# placa_nano.net
KiCad netlist of a schematic drawn in EAGLE
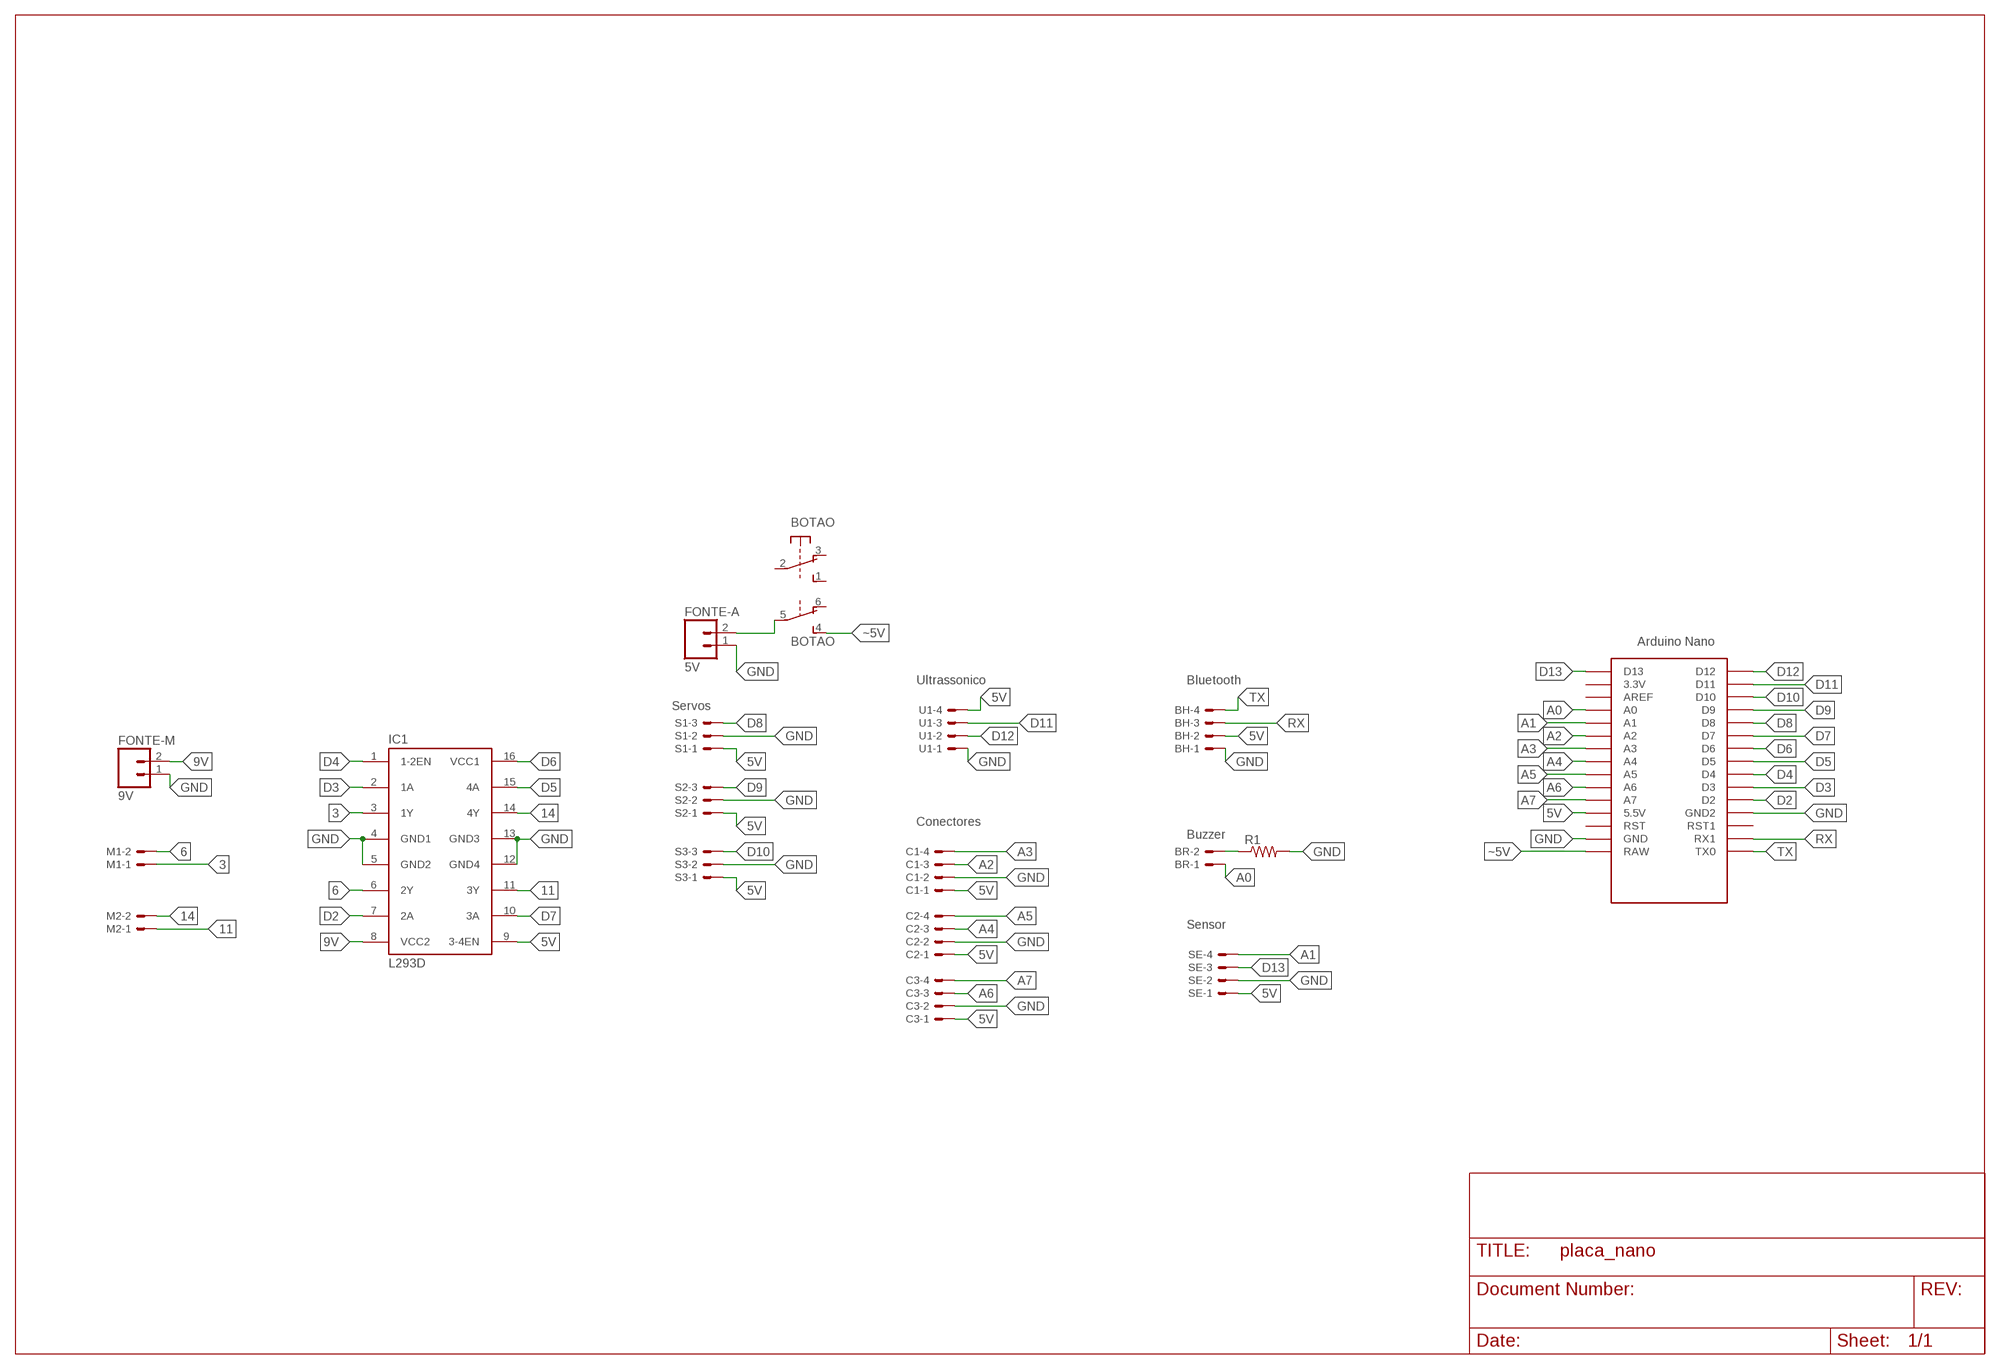
[diagram p0: schematic, sheet 1]

(export (version "E")
  (design (tool "Eeschema 10.0.6"))
  (components
    (comp (ref "BH")
      (value "22-23-2041")
      (footprint "eagle-import:22-23-2041")
      (fields (field (name "MF") "MOLEX"))
      (libsource (lib "eagle-import") (part "22-23-2041"))
    )
    (comp (ref "BOTAO")
      (value "9077-2")
      (footprint "eagle-import:9077-2")
      (libsource (lib "eagle-import") (part "9077-2"))
    )
    (comp (ref "BR")
      (value "22-23-2021")
      (footprint "eagle-import:22-23-2021")
      (fields (field (name "MF") "MOLEX"))
      (libsource (lib "eagle-import") (part "22-23-2021"))
    )
    (comp (ref "C1")
      (value "22-23-2041")
      (footprint "eagle-import:22-23-2041")
      (fields (field (name "MF") "MOLEX"))
      (libsource (lib "eagle-import") (part "22-23-2041"))
    )
    (comp (ref "C2")
      (value "22-23-2041")
      (footprint "eagle-import:22-23-2041")
      (fields (field (name "MF") "MOLEX"))
      (libsource (lib "eagle-import") (part "22-23-2041"))
    )
    (comp (ref "C3")
      (value "22-23-2041")
      (footprint "eagle-import:22-23-2041")
      (fields (field (name "MF") "MOLEX"))
      (libsource (lib "eagle-import") (part "22-23-2041"))
    )
    (comp (ref "FONTE-A")
      (value "5V")
      (footprint "eagle-import:02P")
      (libsource (lib "eagle-import") (part "M02"))
    )
    (comp (ref "FONTE-M")
      (value "9V")
      (footprint "eagle-import:02P")
      (libsource (lib "eagle-import") (part "M02"))
    )
    (comp (ref "IC1")
      (value "L293D")
      (footprint "eagle-import:DIL16")
      (libsource (lib "eagle-import") (part "L293D"))
    )
    (comp (ref "M1")
      (value "22-23-2021")
      (footprint "eagle-import:22-23-2021")
      (fields (field (name "MF") "MOLEX"))
      (libsource (lib "eagle-import") (part "22-23-2021"))
    )
    (comp (ref "M2")
      (value "22-23-2021")
      (footprint "eagle-import:22-23-2021")
      (fields (field (name "MF") "MOLEX"))
      (libsource (lib "eagle-import") (part "22-23-2021"))
    )
    (comp (ref "R1")
      (value "R-US_0207/10")
      (footprint "eagle-import:0207_10")
      (libsource (lib "eagle-import") (part "R-US_0207/10"))
    )
    (comp (ref "S1")
      (value "22-23-2031")
      (footprint "eagle-import:22-23-2031")
      (fields (field (name "MF") "MOLEX"))
      (libsource (lib "eagle-import") (part "22-23-2031"))
    )
    (comp (ref "S2")
      (value "22-23-2031")
      (footprint "eagle-import:22-23-2031")
      (fields (field (name "MF") "MOLEX"))
      (libsource (lib "eagle-import") (part "22-23-2031"))
    )
    (comp (ref "S3")
      (value "22-23-2031")
      (footprint "eagle-import:22-23-2031")
      (fields (field (name "MF") "MOLEX"))
      (libsource (lib "eagle-import") (part "22-23-2031"))
    )
    (comp (ref "SE")
      (value "22-23-2041")
      (footprint "eagle-import:22-23-2041")
      (fields (field (name "MF") "MOLEX"))
      (libsource (lib "eagle-import") (part "22-23-2041"))
    )
    (comp (ref "U$1")
      (value "NANO")
      (footprint "eagle-import:NANO")
      (libsource (lib "eagle-import") (part "NANO"))
    )
    (comp (ref "U1")
      (value "22-23-2041")
      (footprint "eagle-import:22-23-2041")
      (fields (field (name "MF") "MOLEX"))
      (libsource (lib "eagle-import") (part "22-23-2041"))
    )
  )
  (nets
    (net (code "1") (name "/~{5V}") (class "Default")
      (node (ref "BOTAO") (pin "4") (pinfunction "S_4") (pintype "passive"))
      (node (ref "BOTAO") (pin "5") (pinfunction "P_5") (pintype "passive"))
      (node (ref "FONTE-A") (pin "2") (pinfunction "2_2") (pintype "passive"))
      (node (ref "U$1") (pin "RAW") (pinfunction "RAW_RAW") (pintype "bidirectional"))
    )
    (net (code "2") (name "3") (class "Default")
      (node (ref "IC1") (pin "3") (pinfunction "1Y_3") (pintype "output"))
      (node (ref "M1") (pin "1") (pinfunction "S_1") (pintype "passive"))
    )
    (net (code "3") (name "5V") (class "Default")
      (node (ref "BH") (pin "2") (pinfunction "S_2") (pintype "passive"))
      (node (ref "C1") (pin "1") (pinfunction "S_1") (pintype "passive"))
      (node (ref "C2") (pin "1") (pinfunction "S_1") (pintype "passive"))
      (node (ref "C3") (pin "1") (pinfunction "S_1") (pintype "passive"))
      (node (ref "IC1") (pin "9") (pinfunction "3-4EN_9") (pintype "input"))
      (node (ref "S1") (pin "1") (pinfunction "S_1") (pintype "passive"))
      (node (ref "S2") (pin "1") (pinfunction "S_1") (pintype "passive"))
      (node (ref "S3") (pin "1") (pinfunction "S_1") (pintype "passive"))
      (node (ref "SE") (pin "1") (pinfunction "S_1") (pintype "passive"))
      (node (ref "U$1") (pin "5V") (pinfunction "5.5V_5V") (pintype "bidirectional"))
      (node (ref "U1") (pin "4") (pinfunction "S_4") (pintype "passive"))
    )
    (net (code "4") (name "6") (class "Default")
      (node (ref "IC1") (pin "6") (pinfunction "2Y_6") (pintype "output"))
      (node (ref "M1") (pin "2") (pinfunction "S_2") (pintype "passive"))
    )
    (net (code "5") (name "9V") (class "Default")
      (node (ref "FONTE-M") (pin "2") (pinfunction "2_2") (pintype "passive"))
      (node (ref "IC1") (pin "8") (pinfunction "VCC2_8") (pintype "power_in"))
    )
    (net (code "6") (name "11") (class "Default")
      (node (ref "IC1") (pin "11") (pinfunction "3Y_11") (pintype "output"))
      (node (ref "M2") (pin "1") (pinfunction "S_1") (pintype "passive"))
    )
    (net (code "7") (name "14") (class "Default")
      (node (ref "IC1") (pin "14") (pinfunction "4Y_14") (pintype "output"))
      (node (ref "M2") (pin "2") (pinfunction "S_2") (pintype "passive"))
    )
    (net (code "8") (name "A0") (class "Default")
      (node (ref "BR") (pin "1") (pinfunction "S_1") (pintype "passive"))
      (node (ref "U$1") (pin "A0") (pinfunction "A0_A0") (pintype "bidirectional"))
    )
    (net (code "9") (name "A1") (class "Default")
      (node (ref "SE") (pin "4") (pinfunction "S_4") (pintype "passive"))
      (node (ref "U$1") (pin "A1") (pinfunction "A1_A1") (pintype "bidirectional"))
    )
    (net (code "10") (name "A2") (class "Default")
      (node (ref "C1") (pin "3") (pinfunction "S_3") (pintype "passive"))
      (node (ref "U$1") (pin "A2") (pinfunction "A2_A2") (pintype "bidirectional"))
    )
    (net (code "11") (name "A3") (class "Default")
      (node (ref "C1") (pin "4") (pinfunction "S_4") (pintype "passive"))
      (node (ref "U$1") (pin "A3") (pinfunction "A3_A3") (pintype "bidirectional"))
    )
    (net (code "12") (name "A4") (class "Default")
      (node (ref "C2") (pin "3") (pinfunction "S_3") (pintype "passive"))
      (node (ref "U$1") (pin "A4") (pinfunction "A4_A4") (pintype "bidirectional"))
    )
    (net (code "13") (name "A5") (class "Default")
      (node (ref "C2") (pin "4") (pinfunction "S_4") (pintype "passive"))
      (node (ref "U$1") (pin "A5") (pinfunction "A5_A5") (pintype "bidirectional"))
    )
    (net (code "14") (name "A6") (class "Default")
      (node (ref "C3") (pin "3") (pinfunction "S_3") (pintype "passive"))
      (node (ref "U$1") (pin "A6") (pinfunction "A6_A6") (pintype "bidirectional"))
    )
    (net (code "15") (name "A7") (class "Default")
      (node (ref "C3") (pin "4") (pinfunction "S_4") (pintype "passive"))
      (node (ref "U$1") (pin "A7") (pinfunction "A7_A7") (pintype "bidirectional"))
    )
    (net (code "16") (name "D2") (class "Default")
      (node (ref "IC1") (pin "7") (pinfunction "2A_7") (pintype "input"))
      (node (ref "U$1") (pin "D2") (pinfunction "D2_D2") (pintype "bidirectional"))
    )
    (net (code "17") (name "D3") (class "Default")
      (node (ref "IC1") (pin "2") (pinfunction "1A_2") (pintype "input"))
      (node (ref "U$1") (pin "D3") (pinfunction "D3_D3") (pintype "bidirectional"))
    )
    (net (code "18") (name "D4") (class "Default")
      (node (ref "IC1") (pin "1") (pinfunction "1-2EN_1") (pintype "input"))
      (node (ref "U$1") (pin "D4") (pinfunction "D4_D4") (pintype "bidirectional"))
    )
    (net (code "19") (name "D5") (class "Default")
      (node (ref "IC1") (pin "15") (pinfunction "4A_15") (pintype "input"))
      (node (ref "U$1") (pin "D5") (pinfunction "D5_D5") (pintype "bidirectional"))
    )
    (net (code "20") (name "D6") (class "Default")
      (node (ref "IC1") (pin "16") (pinfunction "VCC1_16") (pintype "power_in"))
      (node (ref "U$1") (pin "D6") (pinfunction "D6_D6") (pintype "bidirectional"))
    )
    (net (code "21") (name "D7") (class "Default")
      (node (ref "IC1") (pin "10") (pinfunction "3A_10") (pintype "input"))
      (node (ref "U$1") (pin "D7") (pinfunction "D7_D7") (pintype "bidirectional"))
    )
    (net (code "22") (name "D8") (class "Default")
      (node (ref "S1") (pin "3") (pinfunction "S_3") (pintype "passive"))
      (node (ref "U$1") (pin "D8") (pinfunction "D8_D8") (pintype "bidirectional"))
    )
    (net (code "23") (name "D9") (class "Default")
      (node (ref "S2") (pin "3") (pinfunction "S_3") (pintype "passive"))
      (node (ref "U$1") (pin "D9") (pinfunction "D9_D9") (pintype "bidirectional"))
    )
    (net (code "24") (name "D10") (class "Default")
      (node (ref "S3") (pin "3") (pinfunction "S_3") (pintype "passive"))
      (node (ref "U$1") (pin "D10") (pinfunction "D10_D10") (pintype "bidirectional"))
    )
    (net (code "25") (name "D11") (class "Default")
      (node (ref "U$1") (pin "D11") (pinfunction "D11_D11") (pintype "bidirectional"))
      (node (ref "U1") (pin "3") (pinfunction "S_3") (pintype "passive"))
    )
    (net (code "26") (name "D12") (class "Default")
      (node (ref "U$1") (pin "D12") (pinfunction "D12_D12") (pintype "bidirectional"))
      (node (ref "U1") (pin "2") (pinfunction "S_2") (pintype "passive"))
    )
    (net (code "27") (name "D13") (class "Default")
      (node (ref "SE") (pin "3") (pinfunction "S_3") (pintype "passive"))
      (node (ref "U$1") (pin "D13") (pinfunction "D13_D13") (pintype "bidirectional"))
    )
    (net (code "28") (name "GND") (class "Default")
      (node (ref "BH") (pin "1") (pinfunction "S_1") (pintype "passive"))
      (node (ref "C1") (pin "2") (pinfunction "S_2") (pintype "passive"))
      (node (ref "C2") (pin "2") (pinfunction "S_2") (pintype "passive"))
      (node (ref "C3") (pin "2") (pinfunction "S_2") (pintype "passive"))
      (node (ref "FONTE-A") (pin "1") (pinfunction "1_1") (pintype "passive"))
      (node (ref "FONTE-M") (pin "1") (pinfunction "1_1") (pintype "passive"))
      (node (ref "IC1") (pin "12") (pinfunction "GND4_12") (pintype "power_in"))
      (node (ref "IC1") (pin "13") (pinfunction "GND3_13") (pintype "power_in"))
      (node (ref "IC1") (pin "4") (pinfunction "GND1_4") (pintype "power_in"))
      (node (ref "IC1") (pin "5") (pinfunction "GND2_5") (pintype "power_in"))
      (node (ref "R1") (pin "2") (pinfunction "2_2") (pintype "passive"))
      (node (ref "S1") (pin "2") (pinfunction "S_2") (pintype "passive"))
      (node (ref "S2") (pin "2") (pinfunction "S_2") (pintype "passive"))
      (node (ref "S3") (pin "2") (pinfunction "S_2") (pintype "passive"))
      (node (ref "SE") (pin "2") (pinfunction "S_2") (pintype "passive"))
      (node (ref "U$1") (pin "GND") (pinfunction "GND_GND") (pintype "bidirectional"))
      (node (ref "U$1") (pin "GND1") (pinfunction "GND2_GND1") (pintype "bidirectional"))
      (node (ref "U1") (pin "1") (pinfunction "S_1") (pintype "passive"))
    )
    (net (code "29") (name "Net-(BRB-S)") (class "Default")
      (node (ref "BR") (pin "2") (pinfunction "S_2") (pintype "passive"))
      (node (ref "R1") (pin "1") (pinfunction "1_1") (pintype "passive"))
    )
    (net (code "30") (name "RX") (class "Default")
      (node (ref "BH") (pin "3") (pinfunction "S_3") (pintype "passive"))
      (node (ref "U$1") (pin "RX1") (pinfunction "RX1_RX1") (pintype "bidirectional"))
    )
    (net (code "31") (name "TX") (class "Default")
      (node (ref "BH") (pin "4") (pinfunction "S_4") (pintype "passive"))
      (node (ref "U$1") (pin "TX0") (pinfunction "TX0_TX0") (pintype "bidirectional"))
    )
    (net (code "32") (name "unconnected-(BOTAOA-O-Pad3)") (class "Default")
      (node (ref "BOTAO") (pin "3") (pinfunction "O_3") (pintype "passive"))
    )
    (net (code "33") (name "unconnected-(BOTAOA-P-Pad2)") (class "Default")
      (node (ref "BOTAO") (pin "2") (pinfunction "P_2") (pintype "passive"))
    )
    (net (code "34") (name "unconnected-(BOTAOA-S-Pad1)") (class "Default")
      (node (ref "BOTAO") (pin "1") (pinfunction "S_1") (pintype "passive"))
    )
    (net (code "35") (name "unconnected-(BOTAOB-O-Pad6)") (class "Default")
      (node (ref "BOTAO") (pin "6") (pinfunction "O_6") (pintype "passive"))
    )
    (net (code "36") (name "unconnected-(U$1-Pad3.3V)") (class "Default")
      (node (ref "U$1") (pin "3.3V") (pinfunction "3.3V_3.3V") (pintype "bidirectional"))
    )
    (net (code "37") (name "unconnected-(U$1-PadAREF)") (class "Default")
      (node (ref "U$1") (pin "AREF") (pinfunction "AREF_AREF") (pintype "bidirectional"))
    )
    (net (code "38") (name "unconnected-(U$1-PadRST)") (class "Default")
      (node (ref "U$1") (pin "RST") (pinfunction "RST_RST") (pintype "bidirectional"))
    )
    (net (code "39") (name "unconnected-(U$1-PadRST1)") (class "Default")
      (node (ref "U$1") (pin "RST1") (pinfunction "RST1_RST1") (pintype "bidirectional"))
    )
  )
)
